# HAT_ID02_IMU.net
KiCad netlist of a schematic drawn in Altium Designer
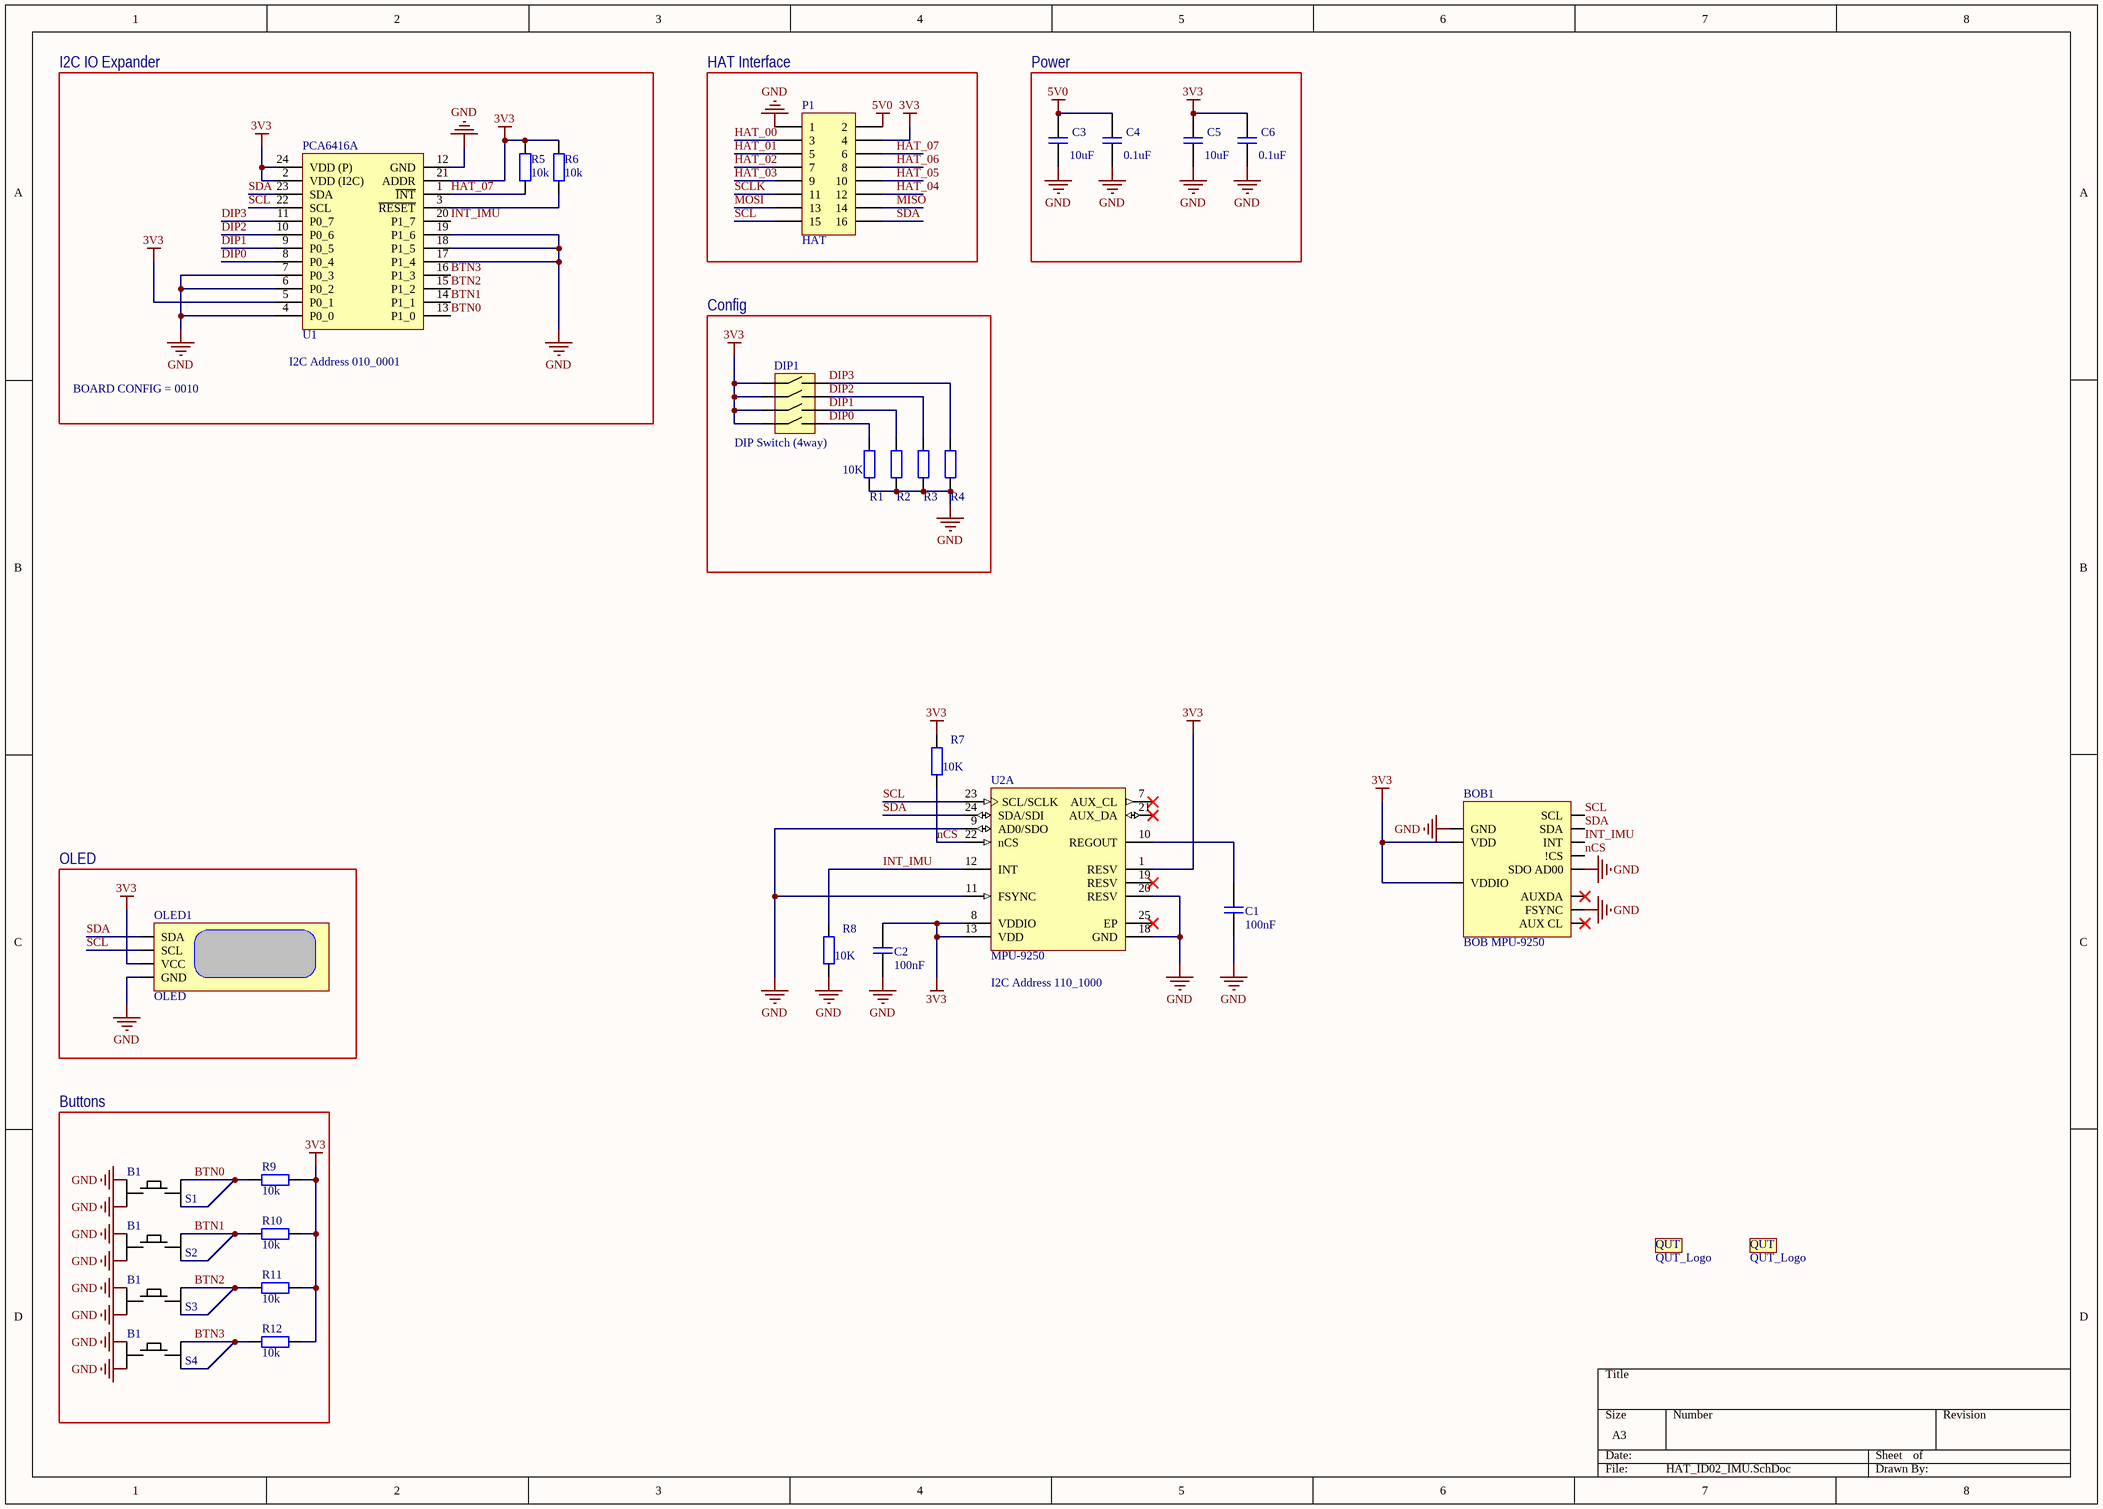
[diagram p0: HAT_ID02_IMU.SchDoc]

(export (version "E")
  (design (tool "Eeschema 10.0.6"))
  (components
    (comp (ref "BOB1")
      (value "BOB MPU-9250")
      (footprint "BOB MPU-9250")
      (libsource (lib "PenguinPi_v2") (part "BOB MPU-9250"))
    )
    (comp (ref "C1")
      (value "100nF")
      (footprint "CAPC2012X07N")
      (description "Surface mount capacitor")
      (fields (field (name "Comment") "CAP SMD"))
      (libsource (lib "Penguin") (part "CAP SMD"))
    )
    (comp (ref "C2")
      (value "100nF")
      (footprint "CAPC2012X07N")
      (description "Surface mount capacitor")
      (fields (field (name "Comment") "CAP SMD"))
      (libsource (lib "Penguin") (part "CAP SMD"))
    )
    (comp (ref "C3")
      (value "10uF")
      (footprint "C0805")
      (description "Surface mount capacitor")
      (fields (field (name "Comment") "CAP SMD"))
      (libsource (lib "Penguin") (part "CAP SMD"))
    )
    (comp (ref "C4")
      (value "0.1uF")
      (footprint "C0805")
      (description "Surface mount capacitor")
      (fields (field (name "Comment") "CAP SMD"))
      (libsource (lib "Penguin") (part "CAP SMD"))
    )
    (comp (ref "C5")
      (value "10uF")
      (footprint "C0805")
      (description "Surface mount capacitor")
      (fields (field (name "Comment") "CAP SMD"))
      (libsource (lib "Penguin") (part "CAP SMD"))
    )
    (comp (ref "C6")
      (value "0.1uF")
      (footprint "C0805")
      (description "Surface mount capacitor")
      (fields (field (name "Comment") "CAP SMD"))
      (libsource (lib "Penguin") (part "CAP SMD"))
    )
    (comp (ref "DIP1")
      (value "DIP Switch (4way)")
      (footprint "DIP SMD")
      (libsource (lib "QUT") (part "DIP Switch (4way)"))
    )
    (comp (ref "LG1") (value "QUT_Logo") (footprint "QUT_Logo") (libsource (lib "Penguin") (part "QUT_Logo")))
    (comp (ref "LG2") (value "QUT_Logo") (footprint "QUT_Logo") (libsource (lib "Penguin") (part "QUT_Logo")))
    (comp (ref "OLED1") (value "OLED") (footprint "OLED") (libsource (lib "PenguinPi_v2") (part "OLED")))
    (comp (ref "P1")
      (value "HAT")
      (footprint "HDR2X8")
      (description "Header, 8-Pin, Dual row")
      (fields (field (name "PUBLISHER") "Altium Limited"))
      (libsource (lib "Miscellaneous Connectors") (part "Header 8X2"))
    )
    (comp (ref "R1")
      (value "10K")
      (footprint "RESC2012X07N")
      (description "0805 surface mount resistor")
      (fields (field (name "Comment") "RES SMD"))
      (libsource (lib "Penguin") (part "RES SMD"))
    )
    (comp (ref "R2")
      (value "RES SMD")
      (footprint "RESC2012X07N")
      (description "0805 surface mount resistor")
      (libsource (lib "Penguin") (part "RES SMD"))
    )
    (comp (ref "R3")
      (value "RES SMD")
      (footprint "RESC2012X07N")
      (description "0805 surface mount resistor")
      (libsource (lib "Penguin") (part "RES SMD"))
    )
    (comp (ref "R4")
      (value "RES SMD")
      (footprint "RESC2012X07N")
      (description "0805 surface mount resistor")
      (libsource (lib "Penguin") (part "RES SMD"))
    )
    (comp (ref "R5")
      (value "10k")
      (footprint "RESC2012X07N")
      (description "0805 surface mount resistor")
      (fields (field (name "Comment") "RES SMD"))
      (libsource (lib "Penguin") (part "RES SMD"))
    )
    (comp (ref "R6")
      (value "10k")
      (footprint "RESC2012X07N")
      (description "0805 surface mount resistor")
      (fields (field (name "Comment") "RES SMD"))
      (libsource (lib "Penguin") (part "RES SMD"))
    )
    (comp (ref "R7")
      (value "10K")
      (footprint "RESC2012X07N")
      (description "0805 surface mount resistor")
      (fields (field (name "Comment") "RES SMD"))
      (libsource (lib "Penguin") (part "RES SMD"))
    )
    (comp (ref "R8")
      (value "10K")
      (footprint "RESC2012X07N")
      (description "0805 surface mount resistor")
      (fields (field (name "Comment") "RES SMD"))
      (libsource (lib "Penguin") (part "RES SMD"))
    )
    (comp (ref "R9")
      (value "10k")
      (footprint "RESC2012X07N")
      (description "0805 surface mount resistor")
      (fields (field (name "Comment") "RES SMD"))
      (libsource (lib "") (part "RES SMD_1"))
    )
    (comp (ref "R10")
      (value "10k")
      (footprint "RESC2012X07N")
      (description "0805 surface mount resistor")
      (fields (field (name "Comment") "RES SMD"))
      (libsource (lib "") (part "RES SMD_1"))
    )
    (comp (ref "R11")
      (value "10k")
      (footprint "RESC2012X07N")
      (description "0805 surface mount resistor")
      (fields (field (name "Comment") "RES SMD"))
      (libsource (lib "") (part "RES SMD_1"))
    )
    (comp (ref "R12")
      (value "10k")
      (footprint "RESC2012X07N")
      (description "0805 surface mount resistor")
      (fields (field (name "Comment") "RES SMD"))
      (libsource (lib "") (part "RES SMD_1"))
    )
    (comp (ref "S1")
      (value "B1")
      (footprint "E-SWITCH-TL3342")
      (description "TL 3342 surface mount pushbutton")
      (libsource (lib "Penguin") (part "E-SWITCH-PUSHBUTTON"))
    )
    (comp (ref "S2")
      (value "B1")
      (footprint "E-SWITCH-TL3342")
      (description "TL 3342 surface mount pushbutton")
      (libsource (lib "Penguin") (part "E-SWITCH-PUSHBUTTON"))
    )
    (comp (ref "S3")
      (value "B1")
      (footprint "E-SWITCH-TL3342")
      (description "TL 3342 surface mount pushbutton")
      (libsource (lib "Penguin") (part "E-SWITCH-PUSHBUTTON"))
    )
    (comp (ref "S4")
      (value "B1")
      (footprint "E-SWITCH-TL3342")
      (description "TL 3342 surface mount pushbutton")
      (libsource (lib "Penguin") (part "E-SWITCH-PUSHBUTTON"))
    )
    (comp (ref "U1")
      (value "PCA6416A")
      (footprint "TSOP65P640X110-24N")
      (description "Low-voltage translating 16-bit I2C I/O port expander")
      (libsource (lib "Penguin") (part "PCA6416APW"))
    )
    (comp (ref "U2")
      (value "MPU-9250")
      (footprint "INSE-QFN-24-1700X1540TP_M")
      (description "9-axis MotionTracking device, 2.4 to 3,6 V, -40 to 85 degC, 24-Pin QFN, RoHS, Tape and Reel")
      (fields (field (name "MANUFACTURER") "InvenSense"))
      (libsource (lib "Altium Content Vault") (part "CMP-2100-03657-1"))
    )
  )
  (nets
    (net (code "1") (name "/BTN0") (class "Default")
      (node (ref "R9") (pin "2") (pinfunction "2_2") (pintype "passive"))
      (node (ref "S1") (pin "3") (pinfunction "B'_3") (pintype "passive"))
      (node (ref "S1") (pin "4") (pinfunction "B_4") (pintype "passive"))
      (node (ref "U1") (pin "13") (pinfunction "P1_0_13") (pintype "passive"))
    )
    (net (code "2") (name "/BTN1") (class "Default")
      (node (ref "R10") (pin "2") (pinfunction "2_2") (pintype "passive"))
      (node (ref "S2") (pin "3") (pinfunction "B'_3") (pintype "passive"))
      (node (ref "S2") (pin "4") (pinfunction "B_4") (pintype "passive"))
      (node (ref "U1") (pin "14") (pinfunction "P1_1_14") (pintype "passive"))
    )
    (net (code "3") (name "/BTN2") (class "Default")
      (node (ref "R11") (pin "2") (pinfunction "2_2") (pintype "passive"))
      (node (ref "S3") (pin "3") (pinfunction "B'_3") (pintype "passive"))
      (node (ref "S3") (pin "4") (pinfunction "B_4") (pintype "passive"))
      (node (ref "U1") (pin "15") (pinfunction "P1_2_15") (pintype "passive"))
    )
    (net (code "4") (name "/BTN3") (class "Default")
      (node (ref "R12") (pin "2") (pinfunction "2_2") (pintype "passive"))
      (node (ref "S4") (pin "3") (pinfunction "B'_3") (pintype "passive"))
      (node (ref "S4") (pin "4") (pinfunction "B_4") (pintype "passive"))
      (node (ref "U1") (pin "16") (pinfunction "P1_3_16") (pintype "passive"))
    )
    (net (code "5") (name "/DIP0") (class "Default")
      (node (ref "DIP1") (pin "4") (pinfunction "4_4") (pintype "passive"))
      (node (ref "R1") (pin "2") (pinfunction "2_2") (pintype "passive"))
      (node (ref "U1") (pin "8") (pinfunction "P0_4_8") (pintype "passive"))
    )
    (net (code "6") (name "/DIP1") (class "Default")
      (node (ref "DIP1") (pin "5") (pinfunction "5_5") (pintype "passive"))
      (node (ref "R2") (pin "2") (pinfunction "2_2") (pintype "passive"))
      (node (ref "U1") (pin "9") (pinfunction "P0_5_9") (pintype "passive"))
    )
    (net (code "7") (name "/DIP2") (class "Default")
      (node (ref "DIP1") (pin "6") (pinfunction "6_6") (pintype "passive"))
      (node (ref "R3") (pin "2") (pinfunction "2_2") (pintype "passive"))
      (node (ref "U1") (pin "10") (pinfunction "P0_6_10") (pintype "passive"))
    )
    (net (code "8") (name "/DIP3") (class "Default")
      (node (ref "DIP1") (pin "7") (pinfunction "7_7") (pintype "passive"))
      (node (ref "R4") (pin "2") (pinfunction "2_2") (pintype "passive"))
      (node (ref "U1") (pin "11") (pinfunction "P0_7_11") (pintype "passive"))
    )
    (net (code "9") (name "/HAT_00") (class "Default")
      (node (ref "P1") (pin "3") (pinfunction "3_3") (pintype "passive"))
    )
    (net (code "10") (name "/HAT_01") (class "Default")
      (node (ref "P1") (pin "5") (pinfunction "5_5") (pintype "passive"))
    )
    (net (code "11") (name "/HAT_02") (class "Default")
      (node (ref "P1") (pin "7") (pinfunction "7_7") (pintype "passive"))
    )
    (net (code "12") (name "/HAT_03") (class "Default")
      (node (ref "P1") (pin "9") (pinfunction "9_9") (pintype "passive"))
    )
    (net (code "13") (name "/HAT_04") (class "Default")
      (node (ref "P1") (pin "12") (pinfunction "12_12") (pintype "passive"))
    )
    (net (code "14") (name "/HAT_05") (class "Default")
      (node (ref "P1") (pin "10") (pinfunction "10_10") (pintype "passive"))
    )
    (net (code "15") (name "/HAT_06") (class "Default")
      (node (ref "P1") (pin "8") (pinfunction "8_8") (pintype "passive"))
    )
    (net (code "16") (name "/HAT_07") (class "Default")
      (node (ref "P1") (pin "6") (pinfunction "6_6") (pintype "passive"))
      (node (ref "R5") (pin "1") (pinfunction "1_1") (pintype "passive"))
      (node (ref "U1") (pin "1") (pinfunction "~{INT}_1") (pintype "passive"))
    )
    (net (code "17") (name "/INT_IMU") (class "Default")
      (node (ref "BOB1") (pin "7") (pinfunction "INT_7") (pintype "passive"))
      (node (ref "R8") (pin "2") (pinfunction "2_2") (pintype "passive"))
      (node (ref "U1") (pin "20") (pinfunction "P1_7_20") (pintype "passive"))
      (node (ref "U2") (pin "12") (pinfunction "INT_12") (pintype "tri_state"))
    )
    (net (code "18") (name "/MISO") (class "Default")
      (node (ref "P1") (pin "14") (pinfunction "14_14") (pintype "passive"))
    )
    (net (code "19") (name "/MOSI") (class "Default")
      (node (ref "P1") (pin "13") (pinfunction "13_13") (pintype "passive"))
    )
    (net (code "20") (name "/SCL") (class "Default")
      (node (ref "BOB1") (pin "0") (pinfunction "SCL_0") (pintype "passive"))
      (node (ref "OLED1") (pin "3") (pinfunction "SCL_3") (pintype "passive"))
      (node (ref "P1") (pin "15") (pinfunction "15_15") (pintype "passive"))
      (node (ref "U1") (pin "22") (pinfunction "SCL_22") (pintype "passive"))
      (node (ref "U2") (pin "23") (pinfunction "SCL/SCLK_23") (pintype "input"))
    )
    (net (code "21") (name "/SCLK") (class "Default")
      (node (ref "P1") (pin "11") (pinfunction "11_11") (pintype "passive"))
    )
    (net (code "22") (name "/SDA") (class "Default")
      (node (ref "BOB1") (pin "1") (pinfunction "SDA_1") (pintype "passive"))
      (node (ref "OLED1") (pin "4") (pinfunction "SDA_4") (pintype "passive"))
      (node (ref "P1") (pin "16") (pinfunction "16_16") (pintype "passive"))
      (node (ref "U1") (pin "23") (pinfunction "SDA_23") (pintype "passive"))
      (node (ref "U2") (pin "24") (pinfunction "SDA/SDI_24") (pintype "bidirectional"))
    )
    (net (code "23") (name "/nCS") (class "Default")
      (node (ref "BOB1") (pin "8") (pinfunction "!CS_8") (pintype "passive"))
      (node (ref "R7") (pin "1") (pinfunction "1_1") (pintype "passive"))
      (node (ref "U2") (pin "22") (pinfunction "nCS_22") (pintype "input"))
    )
    (net (code "24") (name "3V3") (class "Default")
      (node (ref "BOB1") (pin "10") (pinfunction "VDDIO_10") (pintype "passive"))
      (node (ref "BOB1") (pin "2") (pinfunction "VDD_2") (pintype "passive"))
      (node (ref "C2") (pin "2") (pinfunction "K_2") (pintype "passive"))
      (node (ref "C5") (pin "2") (pinfunction "K_2") (pintype "passive"))
      (node (ref "C6") (pin "2") (pinfunction "K_2") (pintype "passive"))
      (node (ref "DIP1") (pin "0") (pinfunction "0_0") (pintype "passive"))
      (node (ref "DIP1") (pin "1") (pinfunction "1_1") (pintype "passive"))
      (node (ref "DIP1") (pin "2") (pinfunction "2_2") (pintype "passive"))
      (node (ref "DIP1") (pin "3") (pinfunction "3_3") (pintype "passive"))
      (node (ref "OLED1") (pin "2") (pinfunction "VCC_2") (pintype "passive"))
      (node (ref "P1") (pin "4") (pinfunction "4_4") (pintype "passive"))
      (node (ref "R10") (pin "1") (pinfunction "1_1") (pintype "passive"))
      (node (ref "R11") (pin "1") (pinfunction "1_1") (pintype "passive"))
      (node (ref "R12") (pin "1") (pinfunction "1_1") (pintype "passive"))
      (node (ref "R5") (pin "2") (pinfunction "2_2") (pintype "passive"))
      (node (ref "R6") (pin "2") (pinfunction "2_2") (pintype "passive"))
      (node (ref "R7") (pin "2") (pinfunction "2_2") (pintype "passive"))
      (node (ref "R9") (pin "1") (pinfunction "1_1") (pintype "passive"))
      (node (ref "U1") (pin "2") (pinfunction "VDD_(I2C)_2") (pintype "passive"))
      (node (ref "U1") (pin "21") (pinfunction "ADDR_21") (pintype "passive"))
      (node (ref "U1") (pin "24") (pinfunction "VDD_(P)_24") (pintype "passive"))
      (node (ref "U1") (pin "5") (pinfunction "P0_1_5") (pintype "passive"))
      (node (ref "U2") (pin "1") (pinfunction "RESV_1") (pintype "power_in"))
      (node (ref "U2") (pin "13") (pinfunction "VDD_13") (pintype "power_in"))
      (node (ref "U2") (pin "8") (pinfunction "VDDIO_8") (pintype "power_in"))
    )
    (net (code "25") (name "5V0") (class "Default")
      (node (ref "C3") (pin "2") (pinfunction "K_2") (pintype "passive"))
      (node (ref "C4") (pin "2") (pinfunction "K_2") (pintype "passive"))
      (node (ref "P1") (pin "2") (pinfunction "2_2") (pintype "passive"))
    )
    (net (code "26") (name "GND") (class "Default")
      (node (ref "BOB1") (pin "3") (pinfunction "GND_3") (pintype "passive"))
      (node (ref "BOB1") (pin "5") (pinfunction "FSYNC_5") (pintype "passive"))
      (node (ref "BOB1") (pin "9") (pinfunction "SDO_AD00_9") (pintype "passive"))
      (node (ref "C1") (pin "1") (pinfunction "A_1") (pintype "passive"))
      (node (ref "C2") (pin "1") (pinfunction "A_1") (pintype "passive"))
      (node (ref "C3") (pin "1") (pinfunction "A_1") (pintype "passive"))
      (node (ref "C4") (pin "1") (pinfunction "A_1") (pintype "passive"))
      (node (ref "C5") (pin "1") (pinfunction "A_1") (pintype "passive"))
      (node (ref "C6") (pin "1") (pinfunction "A_1") (pintype "passive"))
      (node (ref "OLED1") (pin "1") (pinfunction "GND_1") (pintype "passive"))
      (node (ref "P1") (pin "1") (pinfunction "1_1") (pintype "passive"))
      (node (ref "R1") (pin "1") (pinfunction "1_1") (pintype "passive"))
      (node (ref "R2") (pin "1") (pinfunction "1_1") (pintype "passive"))
      (node (ref "R3") (pin "1") (pinfunction "1_1") (pintype "passive"))
      (node (ref "R4") (pin "1") (pinfunction "1_1") (pintype "passive"))
      (node (ref "R8") (pin "1") (pinfunction "1_1") (pintype "passive"))
      (node (ref "S1") (pin "1") (pinfunction "A_1") (pintype "passive"))
      (node (ref "S1") (pin "2") (pinfunction "A'_2") (pintype "passive"))
      (node (ref "S2") (pin "1") (pinfunction "A_1") (pintype "passive"))
      (node (ref "S2") (pin "2") (pinfunction "A'_2") (pintype "passive"))
      (node (ref "S3") (pin "1") (pinfunction "A_1") (pintype "passive"))
      (node (ref "S3") (pin "2") (pinfunction "A'_2") (pintype "passive"))
      (node (ref "S4") (pin "1") (pinfunction "A_1") (pintype "passive"))
      (node (ref "S4") (pin "2") (pinfunction "A'_2") (pintype "passive"))
      (node (ref "U1") (pin "12") (pinfunction "GND_12") (pintype "passive"))
      (node (ref "U1") (pin "17") (pinfunction "P1_4_17") (pintype "passive"))
      (node (ref "U1") (pin "18") (pinfunction "P1_5_18") (pintype "passive"))
      (node (ref "U1") (pin "19") (pinfunction "P1_6_19") (pintype "passive"))
      (node (ref "U1") (pin "4") (pinfunction "P0_0_4") (pintype "passive"))
      (node (ref "U1") (pin "6") (pinfunction "P0_2_6") (pintype "passive"))
      (node (ref "U1") (pin "7") (pinfunction "P0_3_7") (pintype "passive"))
      (node (ref "U2") (pin "11") (pinfunction "FSYNC_11") (pintype "input"))
      (node (ref "U2") (pin "18") (pinfunction "GND_18") (pintype "power_in"))
      (node (ref "U2") (pin "20") (pinfunction "RESV_20") (pintype "power_in"))
      (node (ref "U2") (pin "9") (pinfunction "AD0/SDO_9") (pintype "bidirectional"))
    )
    (net (code "27") (name "Net-(C1-K)") (class "Default")
      (node (ref "C1") (pin "2") (pinfunction "K_2") (pintype "passive"))
      (node (ref "U2") (pin "10") (pinfunction "REGOUT_10") (pintype "passive"))
    )
    (net (code "28") (name "Net-(U1-~{RESET})") (class "Default")
      (node (ref "R6") (pin "1") (pinfunction "1_1") (pintype "passive"))
      (node (ref "U1") (pin "3") (pinfunction "~{RESET}_3") (pintype "passive"))
    )
    (net (code "29") (name "unconnected-(BOB1-AUXDA-Pad4)") (class "Default")
      (node (ref "BOB1") (pin "4") (pinfunction "AUXDA_4") (pintype "passive+no_connect"))
    )
    (net (code "30") (name "unconnected-(BOB1-AUX_CL-Pad6)") (class "Default")
      (node (ref "BOB1") (pin "6") (pinfunction "AUX_CL_6") (pintype "passive+no_connect"))
    )
    (net (code "31") (name "unconnected-(U2A-AUX_CL-Pad7)") (class "Default")
      (node (ref "U2") (pin "7") (pinfunction "AUX_CL_7") (pintype "output+no_connect"))
    )
    (net (code "32") (name "unconnected-(U2A-AUX_DA-Pad21)") (class "Default")
      (node (ref "U2") (pin "21") (pinfunction "AUX_DA_21") (pintype "bidirectional+no_connect"))
    )
    (net (code "33") (name "unconnected-(U2A-EP-Pad25)") (class "Default")
      (node (ref "U2") (pin "25") (pinfunction "EP_25") (pintype "passive+no_connect"))
    )
    (net (code "34") (name "unconnected-(U2A-RESV-Pad19)") (class "Default")
      (node (ref "U2") (pin "19") (pinfunction "RESV_19") (pintype "passive+no_connect"))
    )
  )
)
